# MODULES.net
KiCad netlist of a schematic drawn in Altium Designer
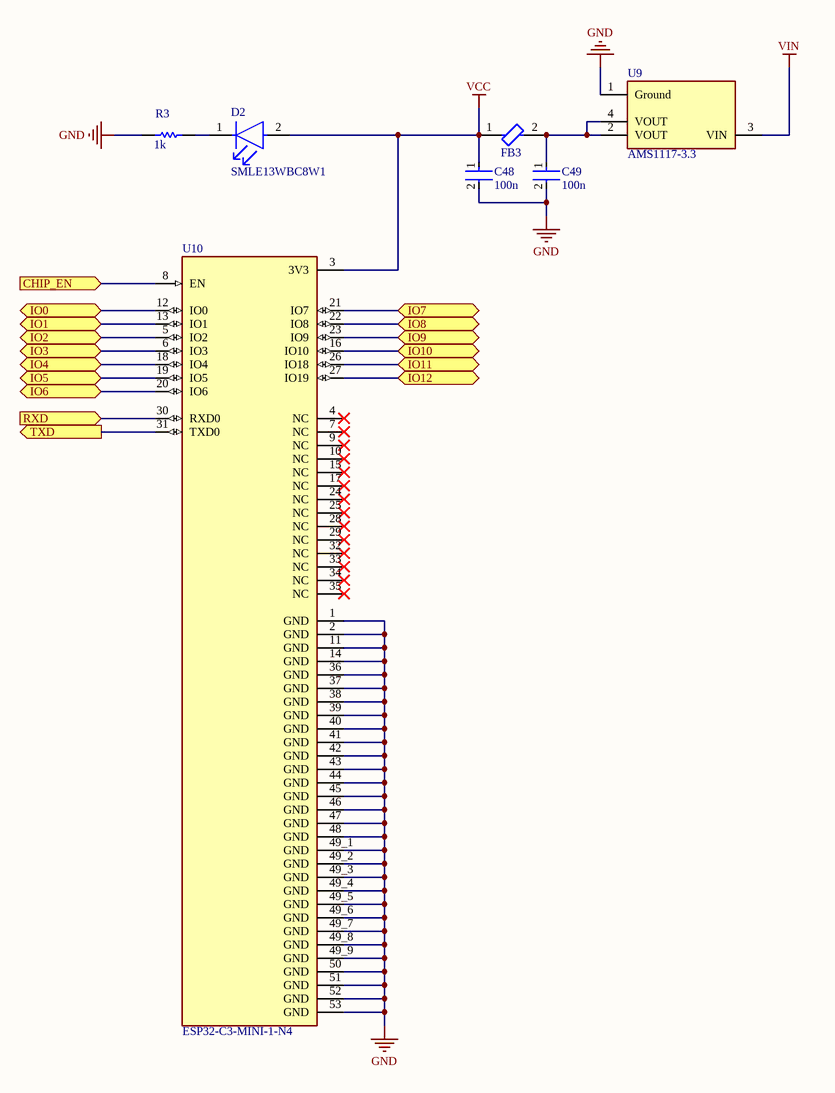
[diagram p0: MODULES.SchDoc]

(export (version "E")
  (design (tool "Eeschema 10.0.6"))
  (components
    (comp (ref "C48")
      (value "100n")
      (footprint "FP-CL10-IPC_C")
      (description "Cap Ceramic 4.7uF 10V X5R ±10% Pad SMD 0603 +85°C T/R")
      (fields (field (name "TOLERANCE") "10%"))
      (libsource (lib "Altium Content Vault") (part "b4654b650e69147ec39a6b967a45e02"))
    )
    (comp (ref "C49")
      (value "100n")
      (footprint "FP-CL10-IPC_C")
      (description "Cap Ceramic 4.7uF 10V X5R ±10% Pad SMD 0603 +85°C T/R")
      (fields (field (name "TOLERANCE") "10%"))
      (libsource (lib "Altium Content Vault") (part "b4654b650e69147ec39a6b967a45e02"))
    )
    (comp (ref "D2")
      (value "SMLE13WBC8W1")
      (footprint "FP-SMLE13WBC8W1-MFG")
      (description "LED WHITE 0603 SMD")
      (fields
        (field (name "OCTOPART") "https://octopart.com/smle13wbc8w1-rohm-22224565")
        (field (name "MANUFACTURER") "Rohm")
      )
      (libsource (lib "Altium Content Vault") (part "8706943c75ba83719d021d2fdc84c58"))
    )
    (comp (ref "FB3")
      (value "BLM18KG121TN1D")
      (footprint "FP-BLM18-0_15-t0_6-d1_2-IPC_A")
      (description "FERRITE BEAD 120 OHM 0603 1LN")
      (fields (field (name "TOLERANCE") "25%"))
      (libsource (lib "Altium Content Vault") (part "5f30dd21d616792df468990f7003faa"))
    )
    (comp (ref "R3")
      (value "1k")
      (footprint "RESC2013X60X35ML10T20")
      (fields (field (name "TOLERANCE") "5%") (field (name "MANUFACTURER") "Yageo"))
      (libsource (lib "Altium Content Vault") (part "RES-2"))
    )
    (comp (ref "U9")
      (value "AMS1117-3.3")
      (footprint "FP-AMS1117-IPC_C")
      (description "LDO Voltage Regulators 1A, 3.3V")
      (fields
        (field (name "OCTOPART") "https://octopart.com/ams1117-3.3-advanced+monolithic+systems-25899300")
        (field (name "MANUFACTURER") "Advanced Monolithic Systems")
      )
      (libsource (lib "Altium Content Vault") (part "8bdbb5f8e77002000e30dd2845d0354"))
    )
    (comp (ref "U10")
      (value "ESP32-C3-MINI-1-N4")
      (footprint "XCVR_ESP32-C3-MINI-1-N4")
      (fields (field (name "MF") "Espressif Systems"))
      (libsource (lib "WIFI-ESP32") (part "ESP32-C3-MINI-1-N4"))
    )
  )
  (nets
    (net (code "1") (name "/CHIP_EN") (class "Default")
      (node (ref "U10") (pin "8") (pinfunction "EN_8") (pintype "input"))
    )
    (net (code "2") (name "/IO0") (class "Default")
      (node (ref "U10") (pin "12") (pinfunction "IO0_12") (pintype "bidirectional"))
    )
    (net (code "3") (name "/IO1") (class "Default")
      (node (ref "U10") (pin "13") (pinfunction "IO1_13") (pintype "bidirectional"))
    )
    (net (code "4") (name "/IO2") (class "Default")
      (node (ref "U10") (pin "5") (pinfunction "IO2_5") (pintype "bidirectional"))
    )
    (net (code "5") (name "/IO3") (class "Default")
      (node (ref "U10") (pin "6") (pinfunction "IO3_6") (pintype "bidirectional"))
    )
    (net (code "6") (name "/IO4") (class "Default")
      (node (ref "U10") (pin "18") (pinfunction "IO4_18") (pintype "bidirectional"))
    )
    (net (code "7") (name "/IO5") (class "Default")
      (node (ref "U10") (pin "19") (pinfunction "IO5_19") (pintype "bidirectional"))
    )
    (net (code "8") (name "/IO6") (class "Default")
      (node (ref "U10") (pin "20") (pinfunction "IO6_20") (pintype "bidirectional"))
    )
    (net (code "9") (name "/IO7") (class "Default")
      (node (ref "U10") (pin "21") (pinfunction "IO7_21") (pintype "bidirectional"))
    )
    (net (code "10") (name "/IO8") (class "Default")
      (node (ref "U10") (pin "22") (pinfunction "IO8_22") (pintype "bidirectional"))
    )
    (net (code "11") (name "/IO9") (class "Default")
      (node (ref "U10") (pin "23") (pinfunction "IO9_23") (pintype "bidirectional"))
    )
    (net (code "12") (name "/IO10") (class "Default")
      (node (ref "U10") (pin "16") (pinfunction "IO10_16") (pintype "bidirectional"))
    )
    (net (code "13") (name "/IO11") (class "Default")
      (node (ref "U10") (pin "26") (pinfunction "IO18_26") (pintype "bidirectional"))
    )
    (net (code "14") (name "/IO12") (class "Default")
      (node (ref "U10") (pin "27") (pinfunction "IO19_27") (pintype "bidirectional"))
    )
    (net (code "15") (name "/RXD") (class "Default")
      (node (ref "U10") (pin "30") (pinfunction "RXD0_30") (pintype "bidirectional"))
    )
    (net (code "16") (name "/TXD") (class "Default")
      (node (ref "U10") (pin "31") (pinfunction "TXD0_31") (pintype "bidirectional"))
    )
    (net (code "17") (name "GND") (class "Default")
      (node (ref "C48") (pin "2") (pinfunction "2_2") (pintype "passive"))
      (node (ref "C49") (pin "2") (pinfunction "2_2") (pintype "passive"))
      (node (ref "R3") (pin "1") (pinfunction "1_1") (pintype "passive"))
      (node (ref "U10") (pin "1") (pinfunction "GND_1") (pintype "power_in"))
      (node (ref "U10") (pin "11") (pinfunction "GND_11") (pintype "power_in"))
      (node (ref "U10") (pin "14") (pinfunction "GND_14") (pintype "power_in"))
      (node (ref "U10") (pin "2") (pinfunction "GND_2") (pintype "power_in"))
      (node (ref "U10") (pin "36") (pinfunction "GND_36") (pintype "power_in"))
      (node (ref "U10") (pin "37") (pinfunction "GND_37") (pintype "power_in"))
      (node (ref "U10") (pin "38") (pinfunction "GND_38") (pintype "power_in"))
      (node (ref "U10") (pin "39") (pinfunction "GND_39") (pintype "power_in"))
      (node (ref "U10") (pin "40") (pinfunction "GND_40") (pintype "power_in"))
      (node (ref "U10") (pin "41") (pinfunction "GND_41") (pintype "power_in"))
      (node (ref "U10") (pin "42") (pinfunction "GND_42") (pintype "power_in"))
      (node (ref "U10") (pin "43") (pinfunction "GND_43") (pintype "power_in"))
      (node (ref "U10") (pin "44") (pinfunction "GND_44") (pintype "power_in"))
      (node (ref "U10") (pin "45") (pinfunction "GND_45") (pintype "power_in"))
      (node (ref "U10") (pin "46") (pinfunction "GND_46") (pintype "power_in"))
      (node (ref "U10") (pin "47") (pinfunction "GND_47") (pintype "power_in"))
      (node (ref "U10") (pin "48") (pinfunction "GND_48") (pintype "power_in"))
      (node (ref "U10") (pin "49_1") (pinfunction "GND_49_1") (pintype "power_in"))
      (node (ref "U10") (pin "49_2") (pinfunction "GND_49_2") (pintype "power_in"))
      (node (ref "U10") (pin "49_3") (pinfunction "GND_49_3") (pintype "power_in"))
      (node (ref "U10") (pin "49_4") (pinfunction "GND_49_4") (pintype "power_in"))
      (node (ref "U10") (pin "49_5") (pinfunction "GND_49_5") (pintype "power_in"))
      (node (ref "U10") (pin "49_6") (pinfunction "GND_49_6") (pintype "power_in"))
      (node (ref "U10") (pin "49_7") (pinfunction "GND_49_7") (pintype "power_in"))
      (node (ref "U10") (pin "49_8") (pinfunction "GND_49_8") (pintype "power_in"))
      (node (ref "U10") (pin "49_9") (pinfunction "GND_49_9") (pintype "power_in"))
      (node (ref "U10") (pin "50") (pinfunction "GND_50") (pintype "power_in"))
      (node (ref "U10") (pin "51") (pinfunction "GND_51") (pintype "power_in"))
      (node (ref "U10") (pin "52") (pinfunction "GND_52") (pintype "power_in"))
      (node (ref "U10") (pin "53") (pinfunction "GND_53") (pintype "power_in"))
      (node (ref "U9") (pin "1") (pinfunction "Ground_1") (pintype "power_in"))
    )
    (net (code "18") (name "Net-(C49-Pad1)") (class "Default")
      (node (ref "C49") (pin "1") (pinfunction "1_1") (pintype "passive"))
      (node (ref "FB3") (pin "2") (pinfunction "2_2") (pintype "passive"))
      (node (ref "U9") (pin "2") (pinfunction "VOUT_2") (pintype "passive"))
      (node (ref "U9") (pin "4") (pinfunction "VOUT_4") (pintype "passive"))
    )
    (net (code "19") (name "Net-(D2-C)") (class "Default")
      (node (ref "D2") (pin "1") (pinfunction "C_1") (pintype "passive"))
      (node (ref "R3") (pin "2") (pinfunction "2_2") (pintype "passive"))
    )
    (net (code "20") (name "VCC") (class "Default")
      (node (ref "C48") (pin "1") (pinfunction "1_1") (pintype "passive"))
      (node (ref "D2") (pin "2") (pinfunction "A_2") (pintype "passive"))
      (node (ref "FB3") (pin "1") (pinfunction "1_1") (pintype "passive"))
      (node (ref "U10") (pin "3") (pinfunction "3V3_3") (pintype "power_in"))
    )
    (net (code "21") (name "VIN") (class "Default")
      (node (ref "U9") (pin "3") (pinfunction "VIN_3") (pintype "power_in"))
    )
    (net (code "22") (name "unconnected-(U10-NC-Pad4)") (class "Default")
      (node (ref "U10") (pin "4") (pinfunction "NC_4") (pintype "passive+no_connect"))
    )
    (net (code "23") (name "unconnected-(U10-NC-Pad7)") (class "Default")
      (node (ref "U10") (pin "7") (pinfunction "NC_7") (pintype "passive+no_connect"))
    )
    (net (code "24") (name "unconnected-(U10-NC-Pad9)") (class "Default")
      (node (ref "U10") (pin "9") (pinfunction "NC_9") (pintype "passive+no_connect"))
    )
    (net (code "25") (name "unconnected-(U10-NC-Pad10)") (class "Default")
      (node (ref "U10") (pin "10") (pinfunction "NC_10") (pintype "passive+no_connect"))
    )
    (net (code "26") (name "unconnected-(U10-NC-Pad15)") (class "Default")
      (node (ref "U10") (pin "15") (pinfunction "NC_15") (pintype "passive+no_connect"))
    )
    (net (code "27") (name "unconnected-(U10-NC-Pad17)") (class "Default")
      (node (ref "U10") (pin "17") (pinfunction "NC_17") (pintype "passive+no_connect"))
    )
    (net (code "28") (name "unconnected-(U10-NC-Pad24)") (class "Default")
      (node (ref "U10") (pin "24") (pinfunction "NC_24") (pintype "passive+no_connect"))
    )
    (net (code "29") (name "unconnected-(U10-NC-Pad25)") (class "Default")
      (node (ref "U10") (pin "25") (pinfunction "NC_25") (pintype "passive+no_connect"))
    )
    (net (code "30") (name "unconnected-(U10-NC-Pad28)") (class "Default")
      (node (ref "U10") (pin "28") (pinfunction "NC_28") (pintype "passive+no_connect"))
    )
    (net (code "31") (name "unconnected-(U10-NC-Pad29)") (class "Default")
      (node (ref "U10") (pin "29") (pinfunction "NC_29") (pintype "passive+no_connect"))
    )
    (net (code "32") (name "unconnected-(U10-NC-Pad32)") (class "Default")
      (node (ref "U10") (pin "32") (pinfunction "NC_32") (pintype "passive+no_connect"))
    )
    (net (code "33") (name "unconnected-(U10-NC-Pad33)") (class "Default")
      (node (ref "U10") (pin "33") (pinfunction "NC_33") (pintype "passive+no_connect"))
    )
    (net (code "34") (name "unconnected-(U10-NC-Pad34)") (class "Default")
      (node (ref "U10") (pin "34") (pinfunction "NC_34") (pintype "passive+no_connect"))
    )
    (net (code "35") (name "unconnected-(U10-NC-Pad35)") (class "Default")
      (node (ref "U10") (pin "35") (pinfunction "NC_35") (pintype "passive+no_connect"))
    )
  )
)
